# main.net
KiCad netlist of a schematic drawn in Altium Designer
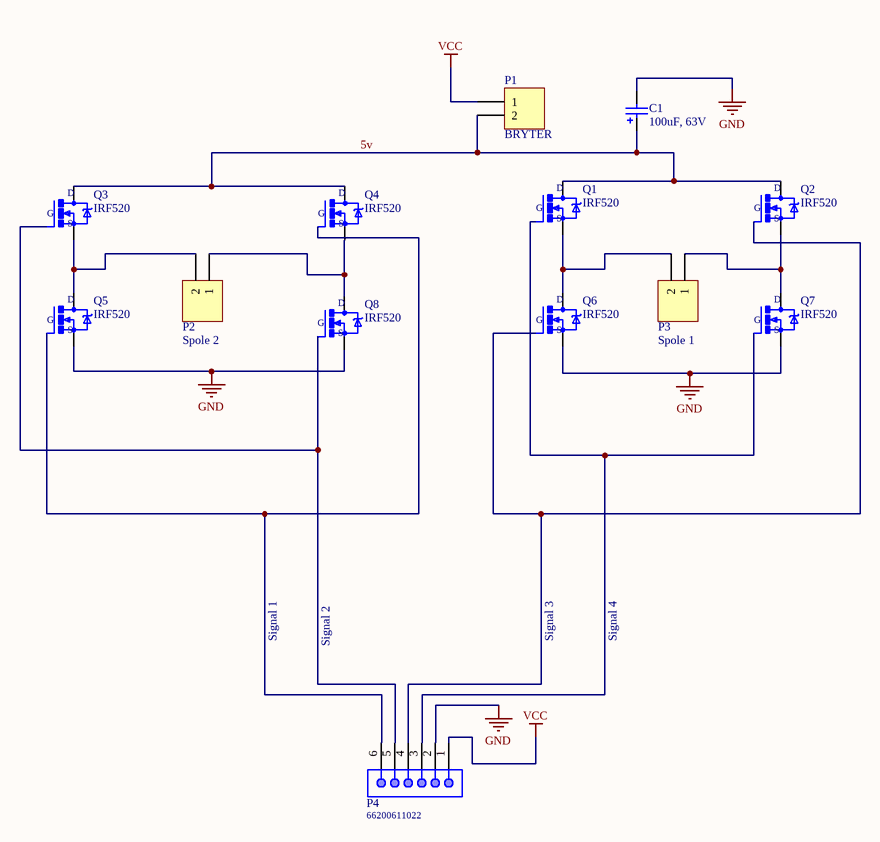
[diagram p0: main.SchDoc]

(export (version "E")
  (design (tool "Eeschema 10.0.6"))
  (components
    (comp (ref "C1")
      (value "100uF, 63V")
      (footprint "WCAP-ATG8_D10H12.5")
      (description "WCAP-ATG8 Aluminum Electrolytic Capacitor, Radial, THT, D10xH12.5, 100uF, 63V")
      (fields
        (field (name "MANUFACTURER PART NUMBER") "860010775014")
        (field (name "MANUFACTURER") "Wurth Elektronik")
      )
      (libsource (lib "WCAP-ATG8") (part "860010775014"))
    )
    (comp (ref "P1")
      (value "BRYTER")
      (footprint "HDR1X2H")
      (description "Header, 2-Pin, Right Angle\r\nBRYTER")
      (fields (field (name "PUBLISHER") "Altium Limited"))
      (libsource (lib "Miscellaneous Connectors") (part "Header 2H"))
    )
    (comp (ref "P2")
      (value "Spole 2")
      (footprint "HDR1X2H")
      (description "Header, 2-Pin, Right Angle\r\nBRYTER")
      (fields (field (name "PUBLISHER") "Altium Limited"))
      (libsource (lib "") (part "Header 2H_1"))
    )
    (comp (ref "P3")
      (value "Spole 1")
      (footprint "HDR1X2H")
      (description "Header, 2-Pin, Right Angle\r\nBRYTER")
      (fields (field (name "PUBLISHER") "Altium Limited"))
      (libsource (lib "") (part "Header 2H_1"))
    )
    (comp (ref "P4")
      (value "66200611022")
      (footprint "66200611022")
      (description "THT Male Header WR-MPC3, with Snap-in Plastic Pegs, Right Angled, Single Row, pitch 3 mm, 6 pins")
      (fields (field (name "PUBLISHER") "Wurth Elektronik"))
      (libsource (lib "WR-MPC3") (part "66200611022"))
    )
    (comp (ref "Q1")
      (value "IRF520")
      (footprint "TO220BV")
      (description "N-Channel 100V 9.2A _Tc_ 60W _Tc_ Through Hole TO-220AB")
      (fields (field (name "MF") "Vishay Siliconix"))
      (libsource (lib "SnapEDAsch") (part "IRF520"))
    )
    (comp (ref "Q2")
      (value "IRF520")
      (footprint "TO220BV")
      (description "N-Channel 100V 9.2A _Tc_ 60W _Tc_ Through Hole TO-220AB")
      (fields (field (name "MF") "Vishay Siliconix"))
      (libsource (lib "SnapEDAsch") (part "IRF520"))
    )
    (comp (ref "Q3")
      (value "IRF520")
      (footprint "TO220BV")
      (description "N-Channel 100V 9.2A _Tc_ 60W _Tc_ Through Hole TO-220AB")
      (fields (field (name "MF") "Vishay Siliconix"))
      (libsource (lib "SnapEDAsch") (part "IRF520"))
    )
    (comp (ref "Q4")
      (value "IRF520")
      (footprint "TO220BV")
      (description "N-Channel 100V 9.2A _Tc_ 60W _Tc_ Through Hole TO-220AB")
      (fields (field (name "MF") "Vishay Siliconix"))
      (libsource (lib "SnapEDAsch") (part "IRF520"))
    )
    (comp (ref "Q5")
      (value "IRF520")
      (footprint "TO220BV")
      (description "N-Channel 100V 9.2A _Tc_ 60W _Tc_ Through Hole TO-220AB")
      (fields (field (name "MF") "Vishay Siliconix"))
      (libsource (lib "SnapEDAsch") (part "IRF520"))
    )
    (comp (ref "Q6")
      (value "IRF520")
      (footprint "TO220BV")
      (description "N-Channel 100V 9.2A _Tc_ 60W _Tc_ Through Hole TO-220AB")
      (fields (field (name "MF") "Vishay Siliconix"))
      (libsource (lib "SnapEDAsch") (part "IRF520"))
    )
    (comp (ref "Q7")
      (value "IRF520")
      (footprint "TO220BV")
      (description "N-Channel 100V 9.2A _Tc_ 60W _Tc_ Through Hole TO-220AB")
      (fields (field (name "MF") "Vishay Siliconix"))
      (libsource (lib "SnapEDAsch") (part "IRF520"))
    )
    (comp (ref "Q8")
      (value "IRF520")
      (footprint "TO220BV")
      (description "N-Channel 100V 9.2A _Tc_ 60W _Tc_ Through Hole TO-220AB")
      (fields (field (name "MF") "Vishay Siliconix"))
      (libsource (lib "SnapEDAsch") (part "IRF520"))
    )
  )
  (nets
    (net (code "1") (name "/5v") (class "Default")
      (node (ref "C1") (pin "1") (pinfunction "P_1") (pintype "passive"))
      (node (ref "P1") (pin "2") (pinfunction "2_2") (pintype "passive"))
      (node (ref "Q1") (pin "D") (pinfunction "D_D") (pintype "passive"))
      (node (ref "Q2") (pin "D") (pinfunction "D_D") (pintype "passive"))
      (node (ref "Q3") (pin "D") (pinfunction "D_D") (pintype "passive"))
      (node (ref "Q4") (pin "D") (pinfunction "D_D") (pintype "passive"))
    )
    (net (code "2") (name "GND") (class "Default")
      (node (ref "C1") (pin "2") (pinfunction "N_2") (pintype "passive"))
      (node (ref "P4") (pin "2") (pinfunction "2_2") (pintype "passive"))
      (node (ref "Q5") (pin "S") (pinfunction "S_S") (pintype "passive"))
      (node (ref "Q6") (pin "S") (pinfunction "S_S") (pintype "passive"))
      (node (ref "Q7") (pin "S") (pinfunction "S_S") (pintype "passive"))
      (node (ref "Q8") (pin "S") (pinfunction "S_S") (pintype "passive"))
    )
    (net (code "3") (name "Net-(P2-Pad1)") (class "Default")
      (node (ref "P2") (pin "1") (pinfunction "1_1") (pintype "passive"))
      (node (ref "Q4") (pin "S") (pinfunction "S_S") (pintype "passive"))
      (node (ref "Q8") (pin "D") (pinfunction "D_D") (pintype "passive"))
    )
    (net (code "4") (name "Net-(P2-Pad2)") (class "Default")
      (node (ref "P2") (pin "2") (pinfunction "2_2") (pintype "passive"))
      (node (ref "Q3") (pin "S") (pinfunction "S_S") (pintype "passive"))
      (node (ref "Q5") (pin "D") (pinfunction "D_D") (pintype "passive"))
    )
    (net (code "5") (name "Net-(P3-Pad1)") (class "Default")
      (node (ref "P3") (pin "1") (pinfunction "1_1") (pintype "passive"))
      (node (ref "Q2") (pin "S") (pinfunction "S_S") (pintype "passive"))
      (node (ref "Q7") (pin "D") (pinfunction "D_D") (pintype "passive"))
    )
    (net (code "6") (name "Net-(P3-Pad2)") (class "Default")
      (node (ref "P3") (pin "2") (pinfunction "2_2") (pintype "passive"))
      (node (ref "Q1") (pin "S") (pinfunction "S_S") (pintype "passive"))
      (node (ref "Q6") (pin "D") (pinfunction "D_D") (pintype "passive"))
    )
    (net (code "7") (name "Net-(P4-Pad3)") (class "Default")
      (node (ref "P4") (pin "3") (pinfunction "3_3") (pintype "passive"))
      (node (ref "Q1") (pin "G") (pinfunction "G_G") (pintype "passive"))
      (node (ref "Q7") (pin "G") (pinfunction "G_G") (pintype "passive"))
    )
    (net (code "8") (name "Net-(P4-Pad4)") (class "Default")
      (node (ref "P4") (pin "4") (pinfunction "4_4") (pintype "passive"))
      (node (ref "Q2") (pin "G") (pinfunction "G_G") (pintype "passive"))
      (node (ref "Q6") (pin "G") (pinfunction "G_G") (pintype "passive"))
    )
    (net (code "9") (name "Net-(P4-Pad5)") (class "Default")
      (node (ref "P4") (pin "5") (pinfunction "5_5") (pintype "passive"))
      (node (ref "Q3") (pin "G") (pinfunction "G_G") (pintype "passive"))
      (node (ref "Q8") (pin "G") (pinfunction "G_G") (pintype "passive"))
    )
    (net (code "10") (name "Net-(P4-Pad6)") (class "Default")
      (node (ref "P4") (pin "6") (pinfunction "6_6") (pintype "passive"))
      (node (ref "Q4") (pin "G") (pinfunction "G_G") (pintype "passive"))
      (node (ref "Q5") (pin "G") (pinfunction "G_G") (pintype "passive"))
    )
    (net (code "11") (name "VCC") (class "Default")
      (node (ref "P1") (pin "1") (pinfunction "1_1") (pintype "passive"))
      (node (ref "P4") (pin "1") (pinfunction "1_1") (pintype "passive"))
    )
  )
)
